# Relay.net
KiCad netlist of a schematic drawn in Altium Designer
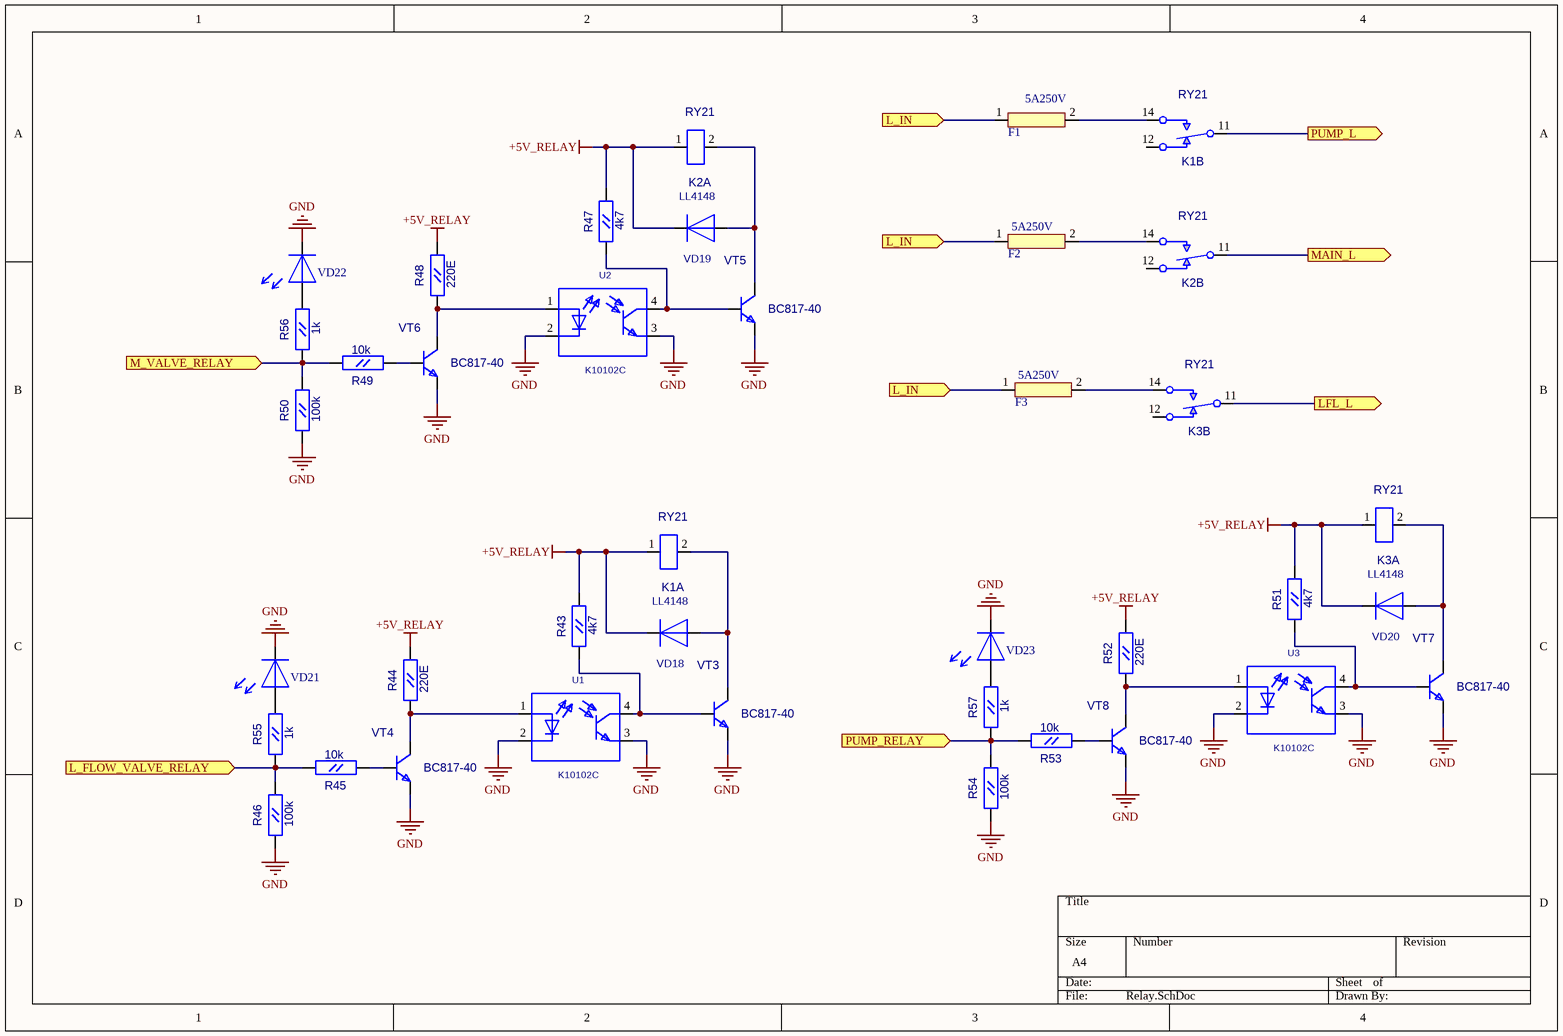
[diagram p0: Relay.SchDoc]

(export (version "E")
  (design (tool "Eeschema 10.0.6"))
  (components
    (comp (ref "F1")
      (value "KLS5-266(5x20) 2pcs")
      (footprint "Fuse_5x20")
      (libsource (lib "gprs_modem_2") (part "Fuse KLS5-266(5x20)"))
    )
    (comp (ref "F2")
      (value "KLS5-266(5x20) 2pcs")
      (footprint "Fuse_5x20")
      (libsource (lib "gprs_modem_2") (part "Fuse KLS5-266(5x20)"))
    )
    (comp (ref "F3")
      (value "KLS5-266(5x20) 2pcs")
      (footprint "Fuse_5x20")
      (libsource (lib "gprs_modem_2") (part "Fuse KLS5-266(5x20)"))
    )
    (comp (ref "K1")
      (value "RY21")
      (footprint "RY21_RY21(Primary)")
      (libsource (lib "shlagbaum") (part "RY21"))
    )
    (comp (ref "K2") (value "RY21") (footprint "RY21_RY21(Primary)") (libsource (lib "") (part "RY21_1")))
    (comp (ref "K3") (value "RY21") (footprint "RY21_RY21(Primary)") (libsource (lib "") (part "RY21_1")))
    (comp (ref "R43")
      (value "4k7")
      (footprint "RC0603")
      (description "RC0603")
      (libsource (lib "gprs_modem_2") (part "RC0603"))
    )
    (comp (ref "R44")
      (value "220E")
      (footprint "RC0603")
      (description "RC0603")
      (libsource (lib "gprs_modem_2") (part "RC0603"))
    )
    (comp (ref "R45")
      (value "10k")
      (footprint "RC0603")
      (description "RC0603")
      (libsource (lib "gprs_modem_2") (part "RC0603"))
    )
    (comp (ref "R46")
      (value "100k")
      (footprint "RC0603")
      (description "RC0603")
      (libsource (lib "gprs_modem_2") (part "RC0603"))
    )
    (comp (ref "R47")
      (value "4k7")
      (footprint "RC0603")
      (description "RC0603")
      (libsource (lib "gprs_modem_2") (part "RC0603"))
    )
    (comp (ref "R48")
      (value "220E")
      (footprint "RC0603")
      (description "RC0603")
      (libsource (lib "gprs_modem_2") (part "RC0603"))
    )
    (comp (ref "R49")
      (value "10k")
      (footprint "RC0603")
      (description "RC0603")
      (libsource (lib "gprs_modem_2") (part "RC0603"))
    )
    (comp (ref "R50")
      (value "100k")
      (footprint "RC0603")
      (description "RC0603")
      (libsource (lib "gprs_modem_2") (part "RC0603"))
    )
    (comp (ref "R51")
      (value "4k7")
      (footprint "RC0603")
      (description "RC0603")
      (libsource (lib "gprs_modem_2") (part "RC0603"))
    )
    (comp (ref "R52")
      (value "220E")
      (footprint "RC0603")
      (description "RC0603")
      (libsource (lib "gprs_modem_2") (part "RC0603"))
    )
    (comp (ref "R53")
      (value "10k")
      (footprint "RC0603")
      (description "RC0603")
      (libsource (lib "gprs_modem_2") (part "RC0603"))
    )
    (comp (ref "R54")
      (value "100k")
      (footprint "RC0603")
      (description "RC0603")
      (libsource (lib "gprs_modem_2") (part "RC0603"))
    )
    (comp (ref "R55")
      (value "1k")
      (footprint "RC0603")
      (description "RC0603")
      (libsource (lib "gprs_modem_2") (part "RC0603"))
    )
    (comp (ref "R56")
      (value "1k")
      (footprint "RC0603")
      (description "RC0603")
      (libsource (lib "gprs_modem_2") (part "RC0603"))
    )
    (comp (ref "R57")
      (value "1k")
      (footprint "RC0603")
      (description "RC0603")
      (libsource (lib "gprs_modem_2") (part "RC0603"))
    )
    (comp (ref "U1") (value "K10102C") (footprint "PC817") (libsource (lib "gprs_modem_2") (part "K10102C")))
    (comp (ref "U2") (value "K10102C") (footprint "PC817") (libsource (lib "gprs_modem_2") (part "K10102C")))
    (comp (ref "U3") (value "K10102C") (footprint "PC817") (libsource (lib "gprs_modem_2") (part "K10102C")))
    (comp (ref "VD18") (value "LL4148") (footprint "SOD-80") (libsource (lib "gprs_modem_2") (part "LL4148")))
    (comp (ref "VD19") (value "LL4148") (footprint "SOD-80") (libsource (lib "gprs_modem_2") (part "LL4148")))
    (comp (ref "VD20") (value "LL4148") (footprint "SOD-80") (libsource (lib "gprs_modem_2") (part "LL4148")))
    (comp (ref "VD21")
      (value "LED_0805")
      (footprint "LED0805")
      (libsource (lib "gprs_modem_2") (part "LED_0805"))
    )
    (comp (ref "VD22")
      (value "LED_0805")
      (footprint "LED0805")
      (libsource (lib "gprs_modem_2") (part "LED_0805"))
    )
    (comp (ref "VD23")
      (value "LED_0805")
      (footprint "LED0805")
      (libsource (lib "gprs_modem_2") (part "LED_0805"))
    )
    (comp (ref "VT3")
      (value "BC817-40")
      (footprint "SOT-23(123)")
      (description "NPN 500ma transistor")
      (libsource (lib "gprs_modem_2") (part "BC846BLT1"))
    )
    (comp (ref "VT4")
      (value "BC817-40")
      (footprint "SOT-23(123)")
      (description "NPN 500ma transistor")
      (libsource (lib "gprs_modem_2") (part "BC846BLT1"))
    )
    (comp (ref "VT5")
      (value "BC817-40")
      (footprint "SOT-23(123)")
      (description "NPN 500ma transistor")
      (libsource (lib "gprs_modem_2") (part "BC846BLT1"))
    )
    (comp (ref "VT6")
      (value "BC817-40")
      (footprint "SOT-23(123)")
      (description "NPN 500ma transistor")
      (libsource (lib "gprs_modem_2") (part "BC846BLT1"))
    )
    (comp (ref "VT7")
      (value "BC817-40")
      (footprint "SOT-23(123)")
      (description "NPN 500ma transistor")
      (libsource (lib "gprs_modem_2") (part "BC846BLT1"))
    )
    (comp (ref "VT8")
      (value "BC817-40")
      (footprint "SOT-23(123)")
      (description "NPN 500ma transistor")
      (libsource (lib "gprs_modem_2") (part "BC846BLT1"))
    )
  )
  (nets
    (net (code "1") (name "+5V_RELAY") (class "Default")
      (node (ref "K1") (pin "1") (pinfunction "L1_1") (pintype "passive"))
      (node (ref "K2") (pin "1") (pinfunction "L1_1") (pintype "passive"))
      (node (ref "K3") (pin "1") (pinfunction "L1_1") (pintype "passive"))
      (node (ref "R43") (pin "2") (pinfunction "B_2") (pintype "passive"))
      (node (ref "R44") (pin "2") (pinfunction "B_2") (pintype "passive"))
      (node (ref "R47") (pin "2") (pinfunction "B_2") (pintype "passive"))
      (node (ref "R48") (pin "2") (pinfunction "B_2") (pintype "passive"))
      (node (ref "R51") (pin "2") (pinfunction "B_2") (pintype "passive"))
      (node (ref "R52") (pin "2") (pinfunction "B_2") (pintype "passive"))
      (node (ref "VD18") (pin "2") (pinfunction "+_2") (pintype "passive"))
      (node (ref "VD19") (pin "2") (pinfunction "+_2") (pintype "passive"))
      (node (ref "VD20") (pin "2") (pinfunction "+_2") (pintype "passive"))
    )
    (net (code "2") (name "/LFL_L") (class "Default")
      (node (ref "K3") (pin "11") (pinfunction "C1_11") (pintype "passive"))
    )
    (net (code "3") (name "/L_FLOW_VALVE_RELAY") (class "Default")
      (node (ref "R45") (pin "2") (pinfunction "B_2") (pintype "passive"))
      (node (ref "R46") (pin "2") (pinfunction "B_2") (pintype "passive"))
      (node (ref "R55") (pin "1") (pinfunction "A_1") (pintype "passive"))
    )
    (net (code "4") (name "/L_IN") (class "Default")
      (node (ref "F1") (pin "1") (pinfunction "9_1") (pintype "passive"))
      (node (ref "F2") (pin "1") (pinfunction "9_1") (pintype "passive"))
      (node (ref "F3") (pin "1") (pinfunction "9_1") (pintype "passive"))
    )
    (net (code "5") (name "/MAIN_L") (class "Default")
      (node (ref "K2") (pin "11") (pinfunction "C1_11") (pintype "passive"))
    )
    (net (code "6") (name "/M_VALVE_RELAY") (class "Default")
      (node (ref "R49") (pin "2") (pinfunction "B_2") (pintype "passive"))
      (node (ref "R50") (pin "2") (pinfunction "B_2") (pintype "passive"))
      (node (ref "R56") (pin "1") (pinfunction "A_1") (pintype "passive"))
    )
    (net (code "7") (name "/PUMP_L") (class "Default")
      (node (ref "K1") (pin "11") (pinfunction "C1_11") (pintype "passive"))
    )
    (net (code "8") (name "/PUMP_RELAY") (class "Default")
      (node (ref "R53") (pin "2") (pinfunction "B_2") (pintype "passive"))
      (node (ref "R54") (pin "2") (pinfunction "B_2") (pintype "passive"))
      (node (ref "R57") (pin "1") (pinfunction "A_1") (pintype "passive"))
    )
    (net (code "9") (name "GND") (class "Default")
      (node (ref "R46") (pin "1") (pinfunction "A_1") (pintype "passive"))
      (node (ref "R50") (pin "1") (pinfunction "A_1") (pintype "passive"))
      (node (ref "R54") (pin "1") (pinfunction "A_1") (pintype "passive"))
      (node (ref "U1") (pin "2") (pintype "passive"))
      (node (ref "U1") (pin "3") (pintype "passive"))
      (node (ref "U2") (pin "2") (pintype "passive"))
      (node (ref "U2") (pin "3") (pintype "passive"))
      (node (ref "U3") (pin "2") (pintype "passive"))
      (node (ref "U3") (pin "3") (pintype "passive"))
      (node (ref "VD21") (pin "2") (pintype "passive"))
      (node (ref "VD22") (pin "2") (pintype "passive"))
      (node (ref "VD23") (pin "2") (pintype "passive"))
      (node (ref "VT3") (pin "2") (pinfunction "E_2") (pintype "passive"))
      (node (ref "VT4") (pin "2") (pinfunction "E_2") (pintype "passive"))
      (node (ref "VT5") (pin "2") (pinfunction "E_2") (pintype "passive"))
      (node (ref "VT6") (pin "2") (pinfunction "E_2") (pintype "passive"))
      (node (ref "VT7") (pin "2") (pinfunction "E_2") (pintype "passive"))
      (node (ref "VT8") (pin "2") (pinfunction "E_2") (pintype "passive"))
    )
    (net (code "10") (name "Net-(K1A-C2)") (class "Default")
      (node (ref "K1") (pin "2") (pinfunction "C2_2") (pintype "passive"))
      (node (ref "VD18") (pin "1") (pinfunction "-_1") (pintype "passive"))
      (node (ref "VT3") (pin "3") (pinfunction "C_3") (pintype "passive"))
    )
    (net (code "11") (name "Net-(K1B-C2)") (class "Default")
      (node (ref "F1") (pin "2") (pinfunction "2_2") (pintype "passive"))
      (node (ref "K1") (pin "14") (pinfunction "C2_14") (pintype "passive"))
    )
    (net (code "12") (name "Net-(K2A-C2)") (class "Default")
      (node (ref "K2") (pin "2") (pinfunction "C2_2") (pintype "passive"))
      (node (ref "VD19") (pin "1") (pinfunction "-_1") (pintype "passive"))
      (node (ref "VT5") (pin "3") (pinfunction "C_3") (pintype "passive"))
    )
    (net (code "13") (name "Net-(K2B-C2)") (class "Default")
      (node (ref "F2") (pin "2") (pinfunction "2_2") (pintype "passive"))
      (node (ref "K2") (pin "14") (pinfunction "C2_14") (pintype "passive"))
    )
    (net (code "14") (name "Net-(K3A-C2)") (class "Default")
      (node (ref "K3") (pin "2") (pinfunction "C2_2") (pintype "passive"))
      (node (ref "VD20") (pin "1") (pinfunction "-_1") (pintype "passive"))
      (node (ref "VT7") (pin "3") (pinfunction "C_3") (pintype "passive"))
    )
    (net (code "15") (name "Net-(K3B-C2)") (class "Default")
      (node (ref "F3") (pin "2") (pinfunction "2_2") (pintype "passive"))
      (node (ref "K3") (pin "14") (pinfunction "C2_14") (pintype "passive"))
    )
    (net (code "16") (name "Net-(R43-A)") (class "Default")
      (node (ref "R43") (pin "1") (pinfunction "A_1") (pintype "passive"))
      (node (ref "U1") (pin "4") (pintype "passive"))
      (node (ref "VT3") (pin "1") (pinfunction "B_1") (pintype "passive"))
    )
    (net (code "17") (name "Net-(R44-A)") (class "Default")
      (node (ref "R44") (pin "1") (pinfunction "A_1") (pintype "passive"))
      (node (ref "U1") (pin "1") (pintype "passive"))
      (node (ref "VT4") (pin "3") (pinfunction "C_3") (pintype "passive"))
    )
    (net (code "18") (name "Net-(R45-A)") (class "Default")
      (node (ref "R45") (pin "1") (pinfunction "A_1") (pintype "passive"))
      (node (ref "VT4") (pin "1") (pinfunction "B_1") (pintype "passive"))
    )
    (net (code "19") (name "Net-(R47-A)") (class "Default")
      (node (ref "R47") (pin "1") (pinfunction "A_1") (pintype "passive"))
      (node (ref "U2") (pin "4") (pintype "passive"))
      (node (ref "VT5") (pin "1") (pinfunction "B_1") (pintype "passive"))
    )
    (net (code "20") (name "Net-(R48-A)") (class "Default")
      (node (ref "R48") (pin "1") (pinfunction "A_1") (pintype "passive"))
      (node (ref "U2") (pin "1") (pintype "passive"))
      (node (ref "VT6") (pin "3") (pinfunction "C_3") (pintype "passive"))
    )
    (net (code "21") (name "Net-(R49-A)") (class "Default")
      (node (ref "R49") (pin "1") (pinfunction "A_1") (pintype "passive"))
      (node (ref "VT6") (pin "1") (pinfunction "B_1") (pintype "passive"))
    )
    (net (code "22") (name "Net-(R51-A)") (class "Default")
      (node (ref "R51") (pin "1") (pinfunction "A_1") (pintype "passive"))
      (node (ref "U3") (pin "4") (pintype "passive"))
      (node (ref "VT7") (pin "1") (pinfunction "B_1") (pintype "passive"))
    )
    (net (code "23") (name "Net-(R52-A)") (class "Default")
      (node (ref "R52") (pin "1") (pinfunction "A_1") (pintype "passive"))
      (node (ref "U3") (pin "1") (pintype "passive"))
      (node (ref "VT8") (pin "3") (pinfunction "C_3") (pintype "passive"))
    )
    (net (code "24") (name "Net-(R53-A)") (class "Default")
      (node (ref "R53") (pin "1") (pinfunction "A_1") (pintype "passive"))
      (node (ref "VT8") (pin "1") (pinfunction "B_1") (pintype "passive"))
    )
    (net (code "25") (name "Net-(R55-B)") (class "Default")
      (node (ref "R55") (pin "2") (pinfunction "B_2") (pintype "passive"))
      (node (ref "VD21") (pin "1") (pintype "passive"))
    )
    (net (code "26") (name "Net-(R56-B)") (class "Default")
      (node (ref "R56") (pin "2") (pinfunction "B_2") (pintype "passive"))
      (node (ref "VD22") (pin "1") (pintype "passive"))
    )
    (net (code "27") (name "Net-(R57-B)") (class "Default")
      (node (ref "R57") (pin "2") (pinfunction "B_2") (pintype "passive"))
      (node (ref "VD23") (pin "1") (pintype "passive"))
    )
    (net (code "28") (name "unconnected-(K1B-C3-Pad12)") (class "Default")
      (node (ref "K1") (pin "12") (pinfunction "C3_12") (pintype "passive"))
    )
    (net (code "29") (name "unconnected-(K2B-C3-Pad12)") (class "Default")
      (node (ref "K2") (pin "12") (pinfunction "C3_12") (pintype "passive"))
    )
    (net (code "30") (name "unconnected-(K3B-C3-Pad12)") (class "Default")
      (node (ref "K3") (pin "12") (pinfunction "C3_12") (pintype "passive"))
    )
  )
)
